# SolarCellX_v2_6milmag.net
KiCad netlist of a schematic drawn in EAGLE
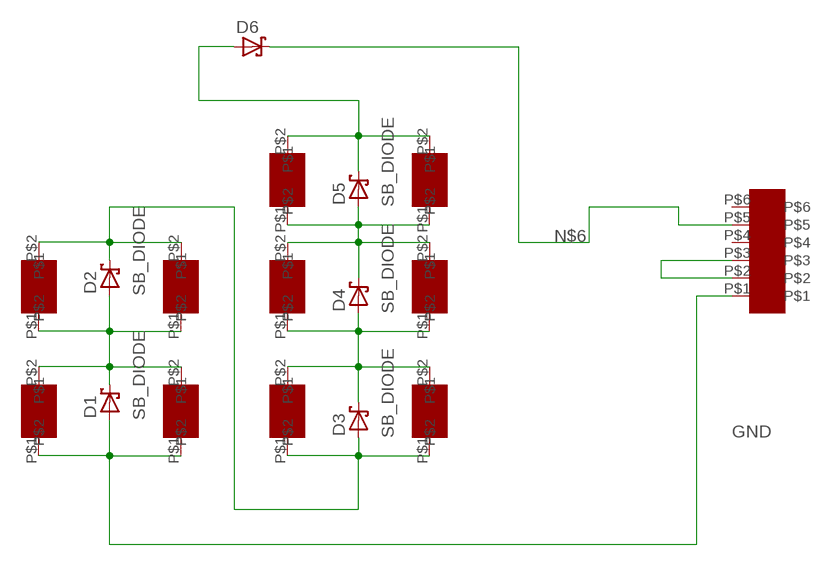
[diagram p0: schematic, sheet 1]

(export (version "E")
  (design (tool "Eeschema 10.0.6"))
  (components
    (comp (ref "1")
      (value "SLMD121H04L")
      (footprint "eagle-import:SLMD121H04L")
      (libsource (lib "eagle-import") (part "SLMD121H04L"))
    )
    (comp (ref "2")
      (value "SLMD121H04L")
      (footprint "eagle-import:SLMD121H04L")
      (libsource (lib "eagle-import") (part "SLMD121H04L"))
    )
    (comp (ref "11")
      (value "SLMD121H04L")
      (footprint "eagle-import:SLMD121H04L")
      (libsource (lib "eagle-import") (part "SLMD121H04L"))
    )
    (comp (ref "12")
      (value "SLMD121H04L")
      (footprint "eagle-import:SLMD121H04L")
      (libsource (lib "eagle-import") (part "SLMD121H04L"))
    )
    (comp (ref "13")
      (value "SLMD121H04L")
      (footprint "eagle-import:SLMD121H04L")
      (libsource (lib "eagle-import") (part "SLMD121H04L"))
    )
    (comp (ref "14")
      (value "SLMD121H04L")
      (footprint "eagle-import:SLMD121H04L")
      (libsource (lib "eagle-import") (part "SLMD121H04L"))
    )
    (comp (ref "21")
      (value "SLMD121H04L")
      (footprint "eagle-import:SLMD121H04L")
      (libsource (lib "eagle-import") (part "SLMD121H04L"))
    )
    (comp (ref "22")
      (value "SLMD121H04L")
      (footprint "eagle-import:SLMD121H04L")
      (libsource (lib "eagle-import") (part "SLMD121H04L"))
    )
    (comp (ref "23")
      (value "SLMD121H04L")
      (footprint "eagle-import:SLMD121H04L")
      (libsource (lib "eagle-import") (part "SLMD121H04L"))
    )
    (comp (ref "24")
      (value "SLMD121H04L")
      (footprint "eagle-import:SLMD121H04L")
      (libsource (lib "eagle-import") (part "SLMD121H04L"))
    )
    (comp (ref "D1")
      (value "SB_DIODE")
      (footprint "eagle-import:SB_DIODE")
      (libsource (lib "eagle-import") (part "SB_DIODE"))
    )
    (comp (ref "D2")
      (value "SB_DIODE")
      (footprint "eagle-import:SB_DIODE")
      (libsource (lib "eagle-import") (part "SB_DIODE"))
    )
    (comp (ref "D3")
      (value "SB_DIODE")
      (footprint "eagle-import:SB_DIODE")
      (libsource (lib "eagle-import") (part "SB_DIODE"))
    )
    (comp (ref "D4")
      (value "SB_DIODE")
      (footprint "eagle-import:SB_DIODE")
      (libsource (lib "eagle-import") (part "SB_DIODE"))
    )
    (comp (ref "D5")
      (value "SB_DIODE")
      (footprint "eagle-import:SB_DIODE")
      (libsource (lib "eagle-import") (part "SB_DIODE"))
    )
    (comp (ref "D6")
      (value "SB_DIODE")
      (footprint "eagle-import:SB_DIODE")
      (libsource (lib "eagle-import") (part "SB_DIODE"))
    )
    (comp (ref "U$1")
      (value "M20-8760342")
      (footprint "eagle-import:M20-8760342")
      (libsource (lib "eagle-import") (part "M20-8760342"))
    )
  )
  (nets
    (net (code "1") (name "/GND") (class "Default")
      (node (ref "11") (pin "P$1") (pinfunction "P$1_P$1") (pintype "bidirectional"))
      (node (ref "12") (pin "P$1") (pinfunction "P$1_P$1") (pintype "bidirectional"))
      (node (ref "D1") (pin "POS") (pinfunction "POS_POS") (pintype "passive"))
      (node (ref "U$1") (pin "P$1") (pinfunction "P$1_P$1") (pintype "bidirectional"))
    )
    (net (code "2") (name "/N$6") (class "Default")
      (node (ref "D6") (pin "NEG") (pinfunction "NEG_NEG") (pintype "passive"))
      (node (ref "U$1") (pin "P$5") (pinfunction "P$5_P$5") (pintype "bidirectional"))
    )
    (net (code "3") (name "Net-(1-PadP$1)") (class "Default")
      (node (ref "1") (pin "P$1") (pinfunction "P$1_P$1") (pintype "bidirectional"))
      (node (ref "2") (pin "P$1") (pinfunction "P$1_P$1") (pintype "bidirectional"))
      (node (ref "23") (pin "P$2") (pinfunction "P$2_P$2") (pintype "bidirectional"))
      (node (ref "24") (pin "P$2") (pinfunction "P$2_P$2") (pintype "bidirectional"))
      (node (ref "D4") (pin "NEG") (pinfunction "NEG_NEG") (pintype "passive"))
      (node (ref "D5") (pin "POS") (pinfunction "POS_POS") (pintype "passive"))
    )
    (net (code "4") (name "Net-(1-PadP$2)") (class "Default")
      (node (ref "1") (pin "P$2") (pinfunction "P$2_P$2") (pintype "bidirectional"))
      (node (ref "2") (pin "P$2") (pinfunction "P$2_P$2") (pintype "bidirectional"))
      (node (ref "D5") (pin "NEG") (pinfunction "NEG_NEG") (pintype "passive"))
      (node (ref "D6") (pin "POS") (pinfunction "POS_POS") (pintype "passive"))
    )
    (net (code "5") (name "Net-(11-PadP$2)") (class "Default")
      (node (ref "11") (pin "P$2") (pinfunction "P$2_P$2") (pintype "bidirectional"))
      (node (ref "12") (pin "P$2") (pinfunction "P$2_P$2") (pintype "bidirectional"))
      (node (ref "13") (pin "P$1") (pinfunction "P$1_P$1") (pintype "bidirectional"))
      (node (ref "14") (pin "P$1") (pinfunction "P$1_P$1") (pintype "bidirectional"))
      (node (ref "D1") (pin "NEG") (pinfunction "NEG_NEG") (pintype "passive"))
      (node (ref "D2") (pin "POS") (pinfunction "POS_POS") (pintype "passive"))
    )
    (net (code "6") (name "Net-(13-PadP$2)") (class "Default")
      (node (ref "13") (pin "P$2") (pinfunction "P$2_P$2") (pintype "bidirectional"))
      (node (ref "14") (pin "P$2") (pinfunction "P$2_P$2") (pintype "bidirectional"))
      (node (ref "21") (pin "P$1") (pinfunction "P$1_P$1") (pintype "bidirectional"))
      (node (ref "22") (pin "P$1") (pinfunction "P$1_P$1") (pintype "bidirectional"))
      (node (ref "D2") (pin "NEG") (pinfunction "NEG_NEG") (pintype "passive"))
      (node (ref "D3") (pin "POS") (pinfunction "POS_POS") (pintype "passive"))
    )
    (net (code "7") (name "Net-(21-PadP$2)") (class "Default")
      (node (ref "21") (pin "P$2") (pinfunction "P$2_P$2") (pintype "bidirectional"))
      (node (ref "22") (pin "P$2") (pinfunction "P$2_P$2") (pintype "bidirectional"))
      (node (ref "23") (pin "P$1") (pinfunction "P$1_P$1") (pintype "bidirectional"))
      (node (ref "24") (pin "P$1") (pinfunction "P$1_P$1") (pintype "bidirectional"))
      (node (ref "D3") (pin "NEG") (pinfunction "NEG_NEG") (pintype "passive"))
      (node (ref "D4") (pin "POS") (pinfunction "POS_POS") (pintype "passive"))
    )
    (net (code "8") (name "Net-(U$1-PadP$2)") (class "Default")
      (node (ref "U$1") (pin "P$2") (pinfunction "P$2_P$2") (pintype "bidirectional"))
      (node (ref "U$1") (pin "P$3") (pinfunction "P$3_P$3") (pintype "bidirectional"))
    )
    (net (code "9") (name "unconnected-(U$1-PadP$4)") (class "Default")
      (node (ref "U$1") (pin "P$4") (pinfunction "P$4_P$4") (pintype "bidirectional"))
    )
    (net (code "10") (name "unconnected-(U$1-PadP$6)") (class "Default")
      (node (ref "U$1") (pin "P$6") (pinfunction "P$6_P$6") (pintype "bidirectional"))
    )
  )
)
